# oil_water_separator2.net
KiCad netlist of a schematic drawn in EAGLE
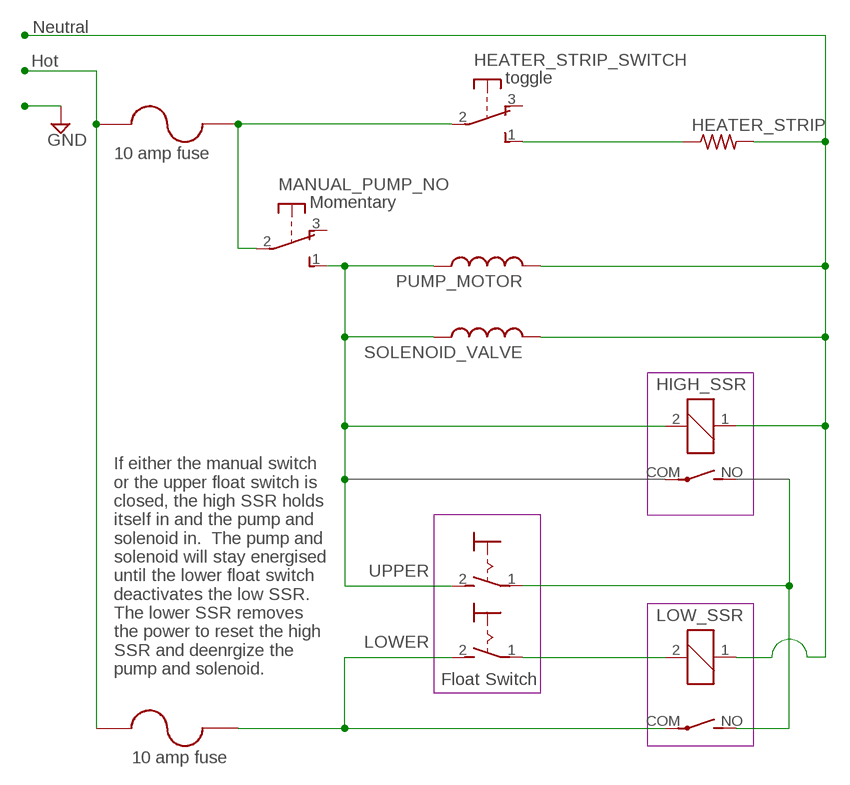
[diagram p0: schematic, sheet 1]

(export (version "E")
  (design (tool "Eeschema 10.0.6"))
  (components
    (comp (ref "HEATER_STRIP")
      (value "RESISITOR0309/V")
      (footprint "eagle-import:0309V")
      (libsource (lib "eagle-import") (part "RESISITOR0309/V"))
    )
    (comp (ref "HEATER_STRIP_SWITCH")
      (value "toggle")
      (footprint "eagle-import:9077-1")
      (libsource (lib "eagle-import") (part "9077-1"))
    )
    (comp (ref "HIGH_SSR")
      (value "APF30212A")
      (footprint "eagle-import:APF30212A")
      (libsource (lib "eagle-import") (part "APF30212A"))
    )
    (comp (ref "LOWER")
      (value "MS243")
      (footprint "eagle-import:MS243")
      (libsource (lib "eagle-import") (part "MS243"))
    )
    (comp (ref "LOW_SSR")
      (value "APF30212A")
      (footprint "eagle-import:APF30212A")
      (libsource (lib "eagle-import") (part "APF30212A"))
    )
    (comp (ref "MANUAL_PUMP_NO")
      (value "Momentary")
      (footprint "eagle-import:9077-1")
      (libsource (lib "eagle-import") (part "9077-1"))
    )
    (comp (ref "PUMP_MOTOR")
      (value "INDUCTOR0204/5")
      (footprint "eagle-import:0204_5")
      (libsource (lib "eagle-import") (part "INDUCTOR0204/5"))
    )
    (comp (ref "SOLENOID_VALVE")
      (value "INDUCTOR0204/5")
      (footprint "eagle-import:0204_5")
      (libsource (lib "eagle-import") (part "INDUCTOR0204/5"))
    )
    (comp (ref "U$1")
      (value "FUSE(SM)")
      (footprint "eagle-import:FUSE")
      (libsource (lib "eagle-import") (part "FUSE(SM)"))
    )
    (comp (ref "U$2")
      (value "FUSE(SM)")
      (footprint "eagle-import:FUSE")
      (libsource (lib "eagle-import") (part "FUSE(SM)"))
    )
    (comp (ref "UPPER")
      (value "MS243")
      (footprint "eagle-import:MS243")
      (libsource (lib "eagle-import") (part "MS243"))
    )
  )
  (nets
    (net (code "2") (name "Net-(HEATER_STRIP-Pad2)") (class "Default")
      (node (ref "HEATER_STRIP") (pin "2") (pinfunction "2_2") (pintype "passive"))
      (node (ref "HIGH_SSR") (pin "1") (pinfunction "1_1") (pintype "passive"))
      (node (ref "LOW_SSR") (pin "1") (pinfunction "1_1") (pintype "passive"))
      (node (ref "PUMP_MOTOR") (pin "2") (pinfunction "2_2") (pintype "passive"))
      (node (ref "SOLENOID_VALVE") (pin "2") (pinfunction "2_2") (pintype "passive"))
    )
    (net (code "3") (name "Net-(HEATER_STRIP_SWITCH-P)") (class "Default")
      (node (ref "HEATER_STRIP_SWITCH") (pin "2") (pinfunction "P_2") (pintype "passive"))
      (node (ref "MANUAL_PUMP_NO") (pin "2") (pinfunction "P_2") (pintype "passive"))
      (node (ref "U$1") (pin "P$2") (pinfunction "P$2_P$2") (pintype "bidirectional"))
    )
    (net (code "4") (name "Net-(HEATER_STRIP_SWITCH-S)") (class "Default")
      (node (ref "HEATER_STRIP") (pin "1") (pinfunction "1_1") (pintype "passive"))
      (node (ref "HEATER_STRIP_SWITCH") (pin "1") (pinfunction "S_1") (pintype "passive"))
    )
    (net (code "5") (name "Net-(LOWER-P)") (class "Default")
      (node (ref "LOWER") (pin "1") (pinfunction "P_1") (pintype "passive"))
      (node (ref "LOW_SSR") (pin "2") (pinfunction "2_2") (pintype "passive"))
    )
    (net (code "6") (name "Net-(LOWER-S)") (class "Default")
      (node (ref "LOWER") (pin "2") (pinfunction "S_2") (pintype "passive"))
      (node (ref "LOW_SSR") (pin "COM") (pinfunction "P_COM") (pintype "passive"))
      (node (ref "U$2") (pin "P$2") (pinfunction "P$2_P$2") (pintype "bidirectional"))
    )
    (net (code "7") (name "Net-(LOW_SSRB-S)") (class "Default")
      (node (ref "LOW_SSR") (pin "NO") (pinfunction "S_NO") (pintype "passive"))
      (node (ref "UPPER") (pin "1") (pinfunction "P_1") (pintype "passive"))
    )
    (net (code "8") (name "Net-(MANUAL_PUMP_NO-S)") (class "Default")
      (node (ref "HIGH_SSR") (pin "2") (pinfunction "2_2") (pintype "passive"))
      (node (ref "MANUAL_PUMP_NO") (pin "1") (pinfunction "S_1") (pintype "passive"))
      (node (ref "PUMP_MOTOR") (pin "1") (pinfunction "1_1") (pintype "passive"))
      (node (ref "SOLENOID_VALVE") (pin "1") (pinfunction "1_1") (pintype "passive"))
      (node (ref "UPPER") (pin "2") (pinfunction "S_2") (pintype "passive"))
    )
    (net (code "9") (name "Net-(U$1-PadP$1)") (class "Default")
      (node (ref "U$1") (pin "P$1") (pinfunction "P$1_P$1") (pintype "bidirectional"))
      (node (ref "U$2") (pin "P$1") (pinfunction "P$1_P$1") (pintype "bidirectional"))
    )
    (net (code "10") (name "unconnected-(HEATER_STRIP_SWITCH-O-Pad3)") (class "Default")
      (node (ref "HEATER_STRIP_SWITCH") (pin "3") (pinfunction "O_3") (pintype "passive"))
    )
    (net (code "11") (name "unconnected-(HIGH_SSRB-P-PadCOM)") (class "Default")
      (node (ref "HIGH_SSR") (pin "COM") (pinfunction "P_COM") (pintype "passive"))
    )
    (net (code "12") (name "unconnected-(HIGH_SSRB-S-PadNO)") (class "Default")
      (node (ref "HIGH_SSR") (pin "NO") (pinfunction "S_NO") (pintype "passive"))
    )
    (net (code "13") (name "unconnected-(MANUAL_PUMP_NO-O-Pad3)") (class "Default")
      (node (ref "MANUAL_PUMP_NO") (pin "3") (pinfunction "O_3") (pintype "passive"))
    )
  )
)
